# sys-part2.net
KiCad netlist of a schematic drawn in Altium Designer
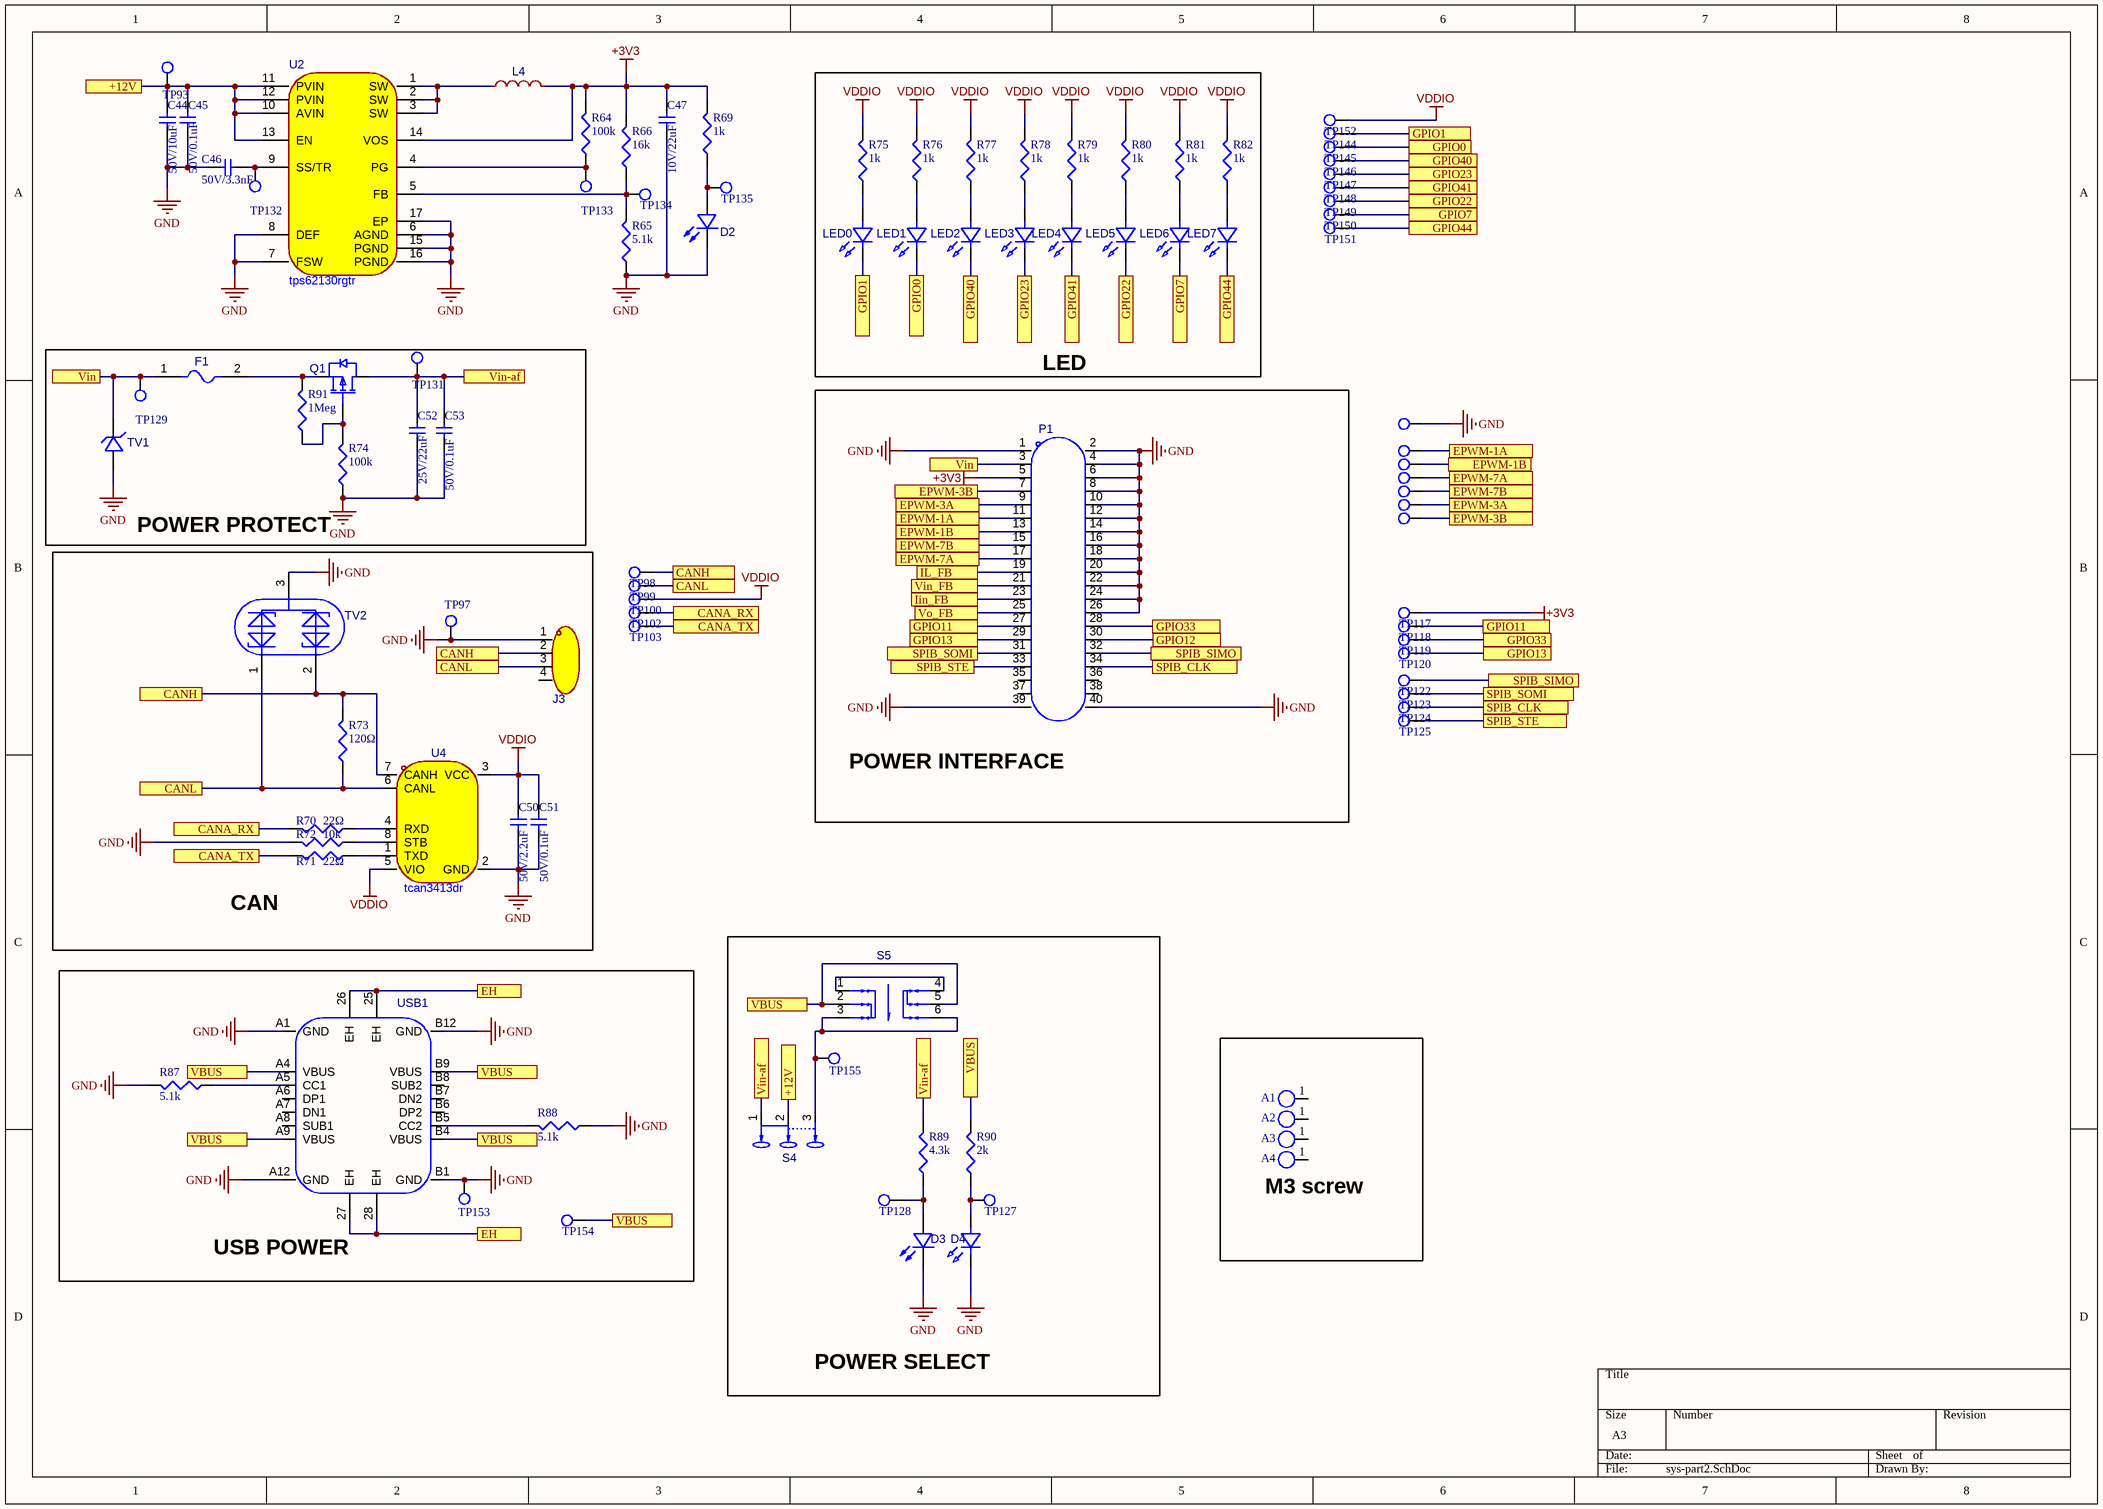
[diagram p0: sys-part2.SchDoc]

(export (version "E")
  (design (tool "Eeschema 10.0.6"))
  (components
    (comp (ref "A1")
      (value "PAD-3.2/6.0")
      (footprint "PAD-3.2/6.0")
      (libsource (lib "60W-PD-V2") (part "PAD-3.2/6.0"))
    )
    (comp (ref "A2")
      (value "PAD-3.2/6.0")
      (footprint "PAD-3.2/6.0")
      (libsource (lib "60W-PD-V2") (part "PAD-3.2/6.0"))
    )
    (comp (ref "A3")
      (value "PAD-3.2/6.0")
      (footprint "PAD-3.2/6.0")
      (libsource (lib "60W-PD-V2") (part "PAD-3.2/6.0"))
    )
    (comp (ref "A4")
      (value "PAD-3.2/6.0")
      (footprint "PAD-3.2/6.0")
      (libsource (lib "60W-PD-V2") (part "PAD-3.2/6.0"))
    )
    (comp (ref "C44")
      (value "50V/10uF")
      (footprint "C0805")
      (description "0805,50V/10uF,")
      (libsource (lib "60W-PD-V2") (part "C0805-50V/10uF"))
    )
    (comp (ref "C45")
      (value "50V/0.1uF")
      (footprint "C0603")
      (description "0603,50V/104")
      (libsource (lib "60W-PD-V2") (part "C0603-50V/104"))
    )
    (comp (ref "C46")
      (value "50V/3.3nF")
      (footprint "C0603")
      (description "0603,50V/3.3nF")
      (libsource (lib "60W-PD-V2") (part "C0603-50V/3.3nF"))
    )
    (comp (ref "C47")
      (value "10V/22uF")
      (footprint "C0603")
      (description "0603,10V/22uF")
      (libsource (lib "60W-PD-V2") (part "C0603-10V/22uF"))
    )
    (comp (ref "C50")
      (value "50V/2.2uF")
      (footprint "C0805")
      (description "0805,50V/2.2uF,")
      (libsource (lib "60W-PD-V2") (part "C0805-50V/2.2uF"))
    )
    (comp (ref "C51")
      (value "50V/0.1uF")
      (footprint "C0603")
      (description "0603,50V/104")
      (libsource (lib "60W-PD-V2") (part "C0603-50V/104"))
    )
    (comp (ref "C52")
      (value "25V/22uF")
      (footprint "C0805")
      (description "0805,25V/22uF,")
      (libsource (lib "60W-PD-V2") (part "C0805-25V/22uF"))
    )
    (comp (ref "C53")
      (value "50V/0.1uF")
      (footprint "C0603")
      (description "0603,50V/104")
      (libsource (lib "60W-PD-V2") (part "C0603-50V/104"))
    )
    (comp (ref "D2")
      (value "ncd0805c1")
      (footprint "LED0805-RD")
      (fields (field (name "MANUFACTURER") "国星光电") (field (name "MANUFACTURERPART") "NCD0805C1"))
      (libsource (lib "60W-PD-V2") (part "ncd0805c1"))
    )
    (comp (ref "D3")
      (value "ncd0805c1")
      (footprint "LED0805-RD")
      (fields (field (name "MANUFACTURER") "国星光电") (field (name "MANUFACTURERPART") "NCD0805C1"))
      (libsource (lib "60W-PD-V2") (part "ncd0805c1"))
    )
    (comp (ref "D4")
      (value "xl-2012surc")
      (footprint "LED0805-RD_RED")
      (fields (field (name "MANUFACTURER") "XINGLIGHT(成兴光)") (field (name "MANUFACTURERPART") "XL-2012SURC"))
      (libsource (lib "60W-PD") (part "xl-2012surc"))
    )
    (comp (ref "F1")
      (value "nsmd050-24v")
      (footprint "F1206")
      (description "耐压(Vmax):24V;最大电流(Imax):100A;保持电流(Ihold):500mA;跳闸电流(Itrip):1A;")
      (fields (field (name "MANUFACTURER") "台湾陆海") (field (name "MANUFACTURERPART") "nSMD050-24V"))
      (libsource (lib "60W-PD-V2") (part "nsmd050-24v"))
    )
    (comp (ref "J3")
      (value "db125-3.81-4p-gn-s")
      (footprint "CONN-TH_DB125-3.81-4P")
      (fields
        (field (name "MANUFACTURER") "DORABO(地博电气)")
        (field (name "MANUFACTURERPART") "DB125-3.81-4P-GN-S")
      )
      (libsource (lib "60W-PD-V2") (part "db125-3.81-4p-gn-s"))
    )
    (comp (ref "L4")
      (value "fhd4020s-3r3mt")
      (footprint "IND-SMD_L4.0-W4.0")
      (description "电感值:3.3uH;精度:±20%;额定电流:4A;饱和电流(Isat):5.9A;类型:绕线电感;")
      (fields (field (name "MANUFACTURER") "cjiang(长江微电)") (field (name "MANUFACTURERPART") "FHD4020S-3R3MT"))
      (libsource (lib "60W-PD-V2") (part "fhd4020s-3r3mt"))
    )
    (comp (ref "LED0")
      (value "xl-2012surc")
      (footprint "LED0805-RD_RED")
      (fields (field (name "MANUFACTURER") "XINGLIGHT(成兴光)") (field (name "MANUFACTURERPART") "XL-2012SURC"))
      (libsource (lib "60W-PD") (part "xl-2012surc"))
    )
    (comp (ref "LED1")
      (value "xl-2012surc")
      (footprint "LED0805-RD_RED")
      (fields (field (name "MANUFACTURER") "XINGLIGHT(成兴光)") (field (name "MANUFACTURERPART") "XL-2012SURC"))
      (libsource (lib "60W-PD") (part "xl-2012surc"))
    )
    (comp (ref "LED2")
      (value "xl-2012surc")
      (footprint "LED0805-RD_RED")
      (fields (field (name "MANUFACTURER") "XINGLIGHT(成兴光)") (field (name "MANUFACTURERPART") "XL-2012SURC"))
      (libsource (lib "60W-PD") (part "xl-2012surc"))
    )
    (comp (ref "LED3")
      (value "xl-2012surc")
      (footprint "LED0805-RD_RED")
      (fields (field (name "MANUFACTURER") "XINGLIGHT(成兴光)") (field (name "MANUFACTURERPART") "XL-2012SURC"))
      (libsource (lib "60W-PD") (part "xl-2012surc"))
    )
    (comp (ref "LED4")
      (value "xl-2012surc")
      (footprint "LED0805-RD_RED")
      (fields (field (name "MANUFACTURER") "XINGLIGHT(成兴光)") (field (name "MANUFACTURERPART") "XL-2012SURC"))
      (libsource (lib "60W-PD") (part "xl-2012surc"))
    )
    (comp (ref "LED5")
      (value "xl-2012surc")
      (footprint "LED0805-RD_RED")
      (fields (field (name "MANUFACTURER") "XINGLIGHT(成兴光)") (field (name "MANUFACTURERPART") "XL-2012SURC"))
      (libsource (lib "60W-PD") (part "xl-2012surc"))
    )
    (comp (ref "LED6")
      (value "xl-2012surc")
      (footprint "LED0805-RD_RED")
      (fields (field (name "MANUFACTURER") "XINGLIGHT(成兴光)") (field (name "MANUFACTURERPART") "XL-2012SURC"))
      (libsource (lib "60W-PD") (part "xl-2012surc"))
    )
    (comp (ref "LED7")
      (value "xl-2012surc")
      (footprint "LED0805-RD_RED")
      (fields (field (name "MANUFACTURER") "XINGLIGHT(成兴光)") (field (name "MANUFACTURERPART") "XL-2012SURC"))
      (libsource (lib "60W-PD") (part "xl-2012surc"))
    )
    (comp (ref "P1")
      (value "zx-pm2.54-2-20py")
      (footprint "HDR-TH_40P-P2.54-V-F-R2-C20-S2.54")
      (fields
        (field (name "MANUFACTURER") "Megastar(兆星)")
        (field (name "MANUFACTURERPART") "ZX-PM2.54-2-20PY")
      )
      (libsource (lib "60W-PD-V2") (part "zx-pm2.54-2-20py"))
    )
    (comp (ref "Q1")
      (value "ao3407a_c15155")
      (footprint "SOT-23-3_L2.9-W1.6-P1.90-LS2.8-BR")
      (fields (field (name "MANUFACTURER") "AOS") (field (name "MANUFACTURERPART") "AO3407A"))
      (libsource (lib "60W-PD-V2") (part "ao3407a_c15155"))
    )
    (comp (ref "R64")
      (value "100k")
      (footprint "R0603")
      (description "0603,100k")
      (libsource (lib "60W-PD-V2") (part "R0603-100k"))
    )
    (comp (ref "R65")
      (value "5.1k")
      (footprint "R0603")
      (description "0603,5.1k")
      (libsource (lib "60W-PD-V2") (part "R0603-5.1k"))
    )
    (comp (ref "R66")
      (value "16k")
      (footprint "R0603")
      (description "0603,16k")
      (libsource (lib "60W-PD-V2") (part "R0603-16k"))
    )
    (comp (ref "R69")
      (value "1k")
      (footprint "R0603")
      (description "0603,1k")
      (libsource (lib "60W-PD-V2") (part "R0603-1k"))
    )
    (comp (ref "R70")
      (value "22Ω")
      (footprint "R0603")
      (description "0603,22Ω")
      (libsource (lib "60W-PD-V2") (part "R0603-22Ω"))
    )
    (comp (ref "R71")
      (value "22Ω")
      (footprint "R0603")
      (description "0603,22Ω")
      (libsource (lib "60W-PD-V2") (part "R0603-22Ω"))
    )
    (comp (ref "R72")
      (value "10k")
      (footprint "R0603")
      (description "0603,10k")
      (libsource (lib "60W-PD-V2") (part "R0603-10k"))
    )
    (comp (ref "R73")
      (value "120Ω")
      (footprint "R0603")
      (description "0603,120Ω")
      (libsource (lib "60W-PD-V2") (part "R0603-120Ω"))
    )
    (comp (ref "R74")
      (value "100k")
      (footprint "R0603")
      (description "0603,100k")
      (libsource (lib "60W-PD-V2") (part "R0603-100k"))
    )
    (comp (ref "R75")
      (value "1k")
      (footprint "R0603")
      (description "0603,1k")
      (libsource (lib "60W-PD-V2") (part "R0603-1k"))
    )
    (comp (ref "R76")
      (value "1k")
      (footprint "R0603")
      (description "0603,1k")
      (libsource (lib "60W-PD-V2") (part "R0603-1k"))
    )
    (comp (ref "R77")
      (value "1k")
      (footprint "R0603")
      (description "0603,1k")
      (libsource (lib "60W-PD-V2") (part "R0603-1k"))
    )
    (comp (ref "R78")
      (value "1k")
      (footprint "R0603")
      (description "0603,1k")
      (libsource (lib "60W-PD-V2") (part "R0603-1k"))
    )
    (comp (ref "R79")
      (value "1k")
      (footprint "R0603")
      (description "0603,1k")
      (libsource (lib "60W-PD-V2") (part "R0603-1k"))
    )
    (comp (ref "R80")
      (value "1k")
      (footprint "R0603")
      (description "0603,1k")
      (libsource (lib "60W-PD-V2") (part "R0603-1k"))
    )
    (comp (ref "R81")
      (value "1k")
      (footprint "R0603")
      (description "0603,1k")
      (libsource (lib "60W-PD-V2") (part "R0603-1k"))
    )
    (comp (ref "R82")
      (value "1k")
      (footprint "R0603")
      (description "0603,1k")
      (libsource (lib "60W-PD-V2") (part "R0603-1k"))
    )
    (comp (ref "R87")
      (value "5.1k")
      (footprint "R0603")
      (description "0603,5.1k")
      (libsource (lib "60W-PD-V2") (part "R0603-5.1k"))
    )
    (comp (ref "R88")
      (value "5.1k")
      (footprint "R0603")
      (description "0603,5.1k")
      (libsource (lib "60W-PD-V2") (part "R0603-5.1k"))
    )
    (comp (ref "R89")
      (value "4.3k")
      (footprint "R0603")
      (description "0603,4.3k")
      (libsource (lib "60W-PD-V2") (part "R0603-4.3k"))
    )
    (comp (ref "R90")
      (value "2k")
      (footprint "R0603")
      (description "0603,2k")
      (libsource (lib "60W-PD-V2") (part "R0603-2k"))
    )
    (comp (ref "R91")
      (value "1Meg")
      (footprint "R0603")
      (description "0603,1Meg")
      (libsource (lib "60W-PD-V2") (part "R0603-1Meg"))
    )
    (comp (ref "S4")
      (value "ss-12d10l5")
      (footprint "SW-TH_SS-12D10L5")
      (description "电路结构:单刀双掷;安装方式:直插;开关颜色:黑色;额定电流:3A;额定电压:125V;工作寿命:1万次;")
      (fields
        (field (name "MANUFACTURER") "XKB Connection(中国星坤)")
        (field (name "MANUFACTURERPART") "SS-12D10L5")
      )
      (libsource (lib "60W-PD") (part "ss-12d10l5"))
    )
    (comp (ref "S5")
      (value "xkb8080-z")
      (footprint "SW-TH_6P-L8.0-W8.0-P2.50")
      (description "自锁/无锁:自锁;安装方式:直插;触点电流:100mA;额定电压:30V;带灯:不带;作用力:1.6N;工作寿命:10万次;")
      (fields
        (field (name "MANUFACTURER") "XKB Connection(中国星坤)")
        (field (name "MANUFACTURERPART") "XKB8080-Z")
      )
      (libsource (lib "60W-PD-V2") (part "xkb8080-z"))
    )
    (comp (ref "TP93")
      (value "TEST POINT")
      (footprint "TP-1.5")
      (libsource (lib "60W-PD") (part "TEST POINT"))
    )
    (comp (ref "TP97")
      (value "TP-pad0.8")
      (footprint "PAD0.8/1.6")
      (libsource (lib "60W-PD-V2") (part "TP-pad0.8"))
    )
    (comp (ref "TP98")
      (value "TEST POINT")
      (footprint "TP-1.5")
      (libsource (lib "60W-PD") (part "TEST POINT"))
    )
    (comp (ref "TP99")
      (value "TEST POINT")
      (footprint "TP-1.5")
      (libsource (lib "60W-PD") (part "TEST POINT"))
    )
    (comp (ref "TP100")
      (value "TEST POINT")
      (footprint "TP-1.5")
      (libsource (lib "60W-PD") (part "TEST POINT"))
    )
    (comp (ref "TP102")
      (value "TEST POINT")
      (footprint "TP-1.5")
      (libsource (lib "60W-PD") (part "TEST POINT"))
    )
    (comp (ref "TP103")
      (value "TEST POINT")
      (footprint "TP-1.5")
      (libsource (lib "60W-PD") (part "TEST POINT"))
    )
    (comp (ref "TP104")
      (value "TP-pad0.8")
      (footprint "PAD0.8/1.6")
      (libsource (lib "60W-PD-V2") (part "TP-pad0.8"))
    )
    (comp (ref "TP105")
      (value "TP-pad0.8")
      (footprint "PAD0.8/1.6")
      (libsource (lib "60W-PD-V2") (part "TP-pad0.8"))
    )
    (comp (ref "TP106")
      (value "TP-pad0.8")
      (footprint "PAD0.8/1.6")
      (libsource (lib "60W-PD-V2") (part "TP-pad0.8"))
    )
    (comp (ref "TP107")
      (value "TP-pad0.8")
      (footprint "PAD0.8/1.6")
      (libsource (lib "60W-PD-V2") (part "TP-pad0.8"))
    )
    (comp (ref "TP108")
      (value "TP-pad0.8")
      (footprint "PAD0.8/1.6")
      (libsource (lib "60W-PD-V2") (part "TP-pad0.8"))
    )
    (comp (ref "TP109")
      (value "TP-pad0.8")
      (footprint "PAD0.8/1.6")
      (libsource (lib "60W-PD-V2") (part "TP-pad0.8"))
    )
    (comp (ref "TP110")
      (value "TP-pad0.8")
      (footprint "PAD0.8/1.6")
      (libsource (lib "60W-PD-V2") (part "TP-pad0.8"))
    )
    (comp (ref "TP117")
      (value "TEST POINT")
      (footprint "TP-1.5")
      (libsource (lib "60W-PD") (part "TEST POINT"))
    )
    (comp (ref "TP118")
      (value "TEST POINT")
      (footprint "TP-1.5")
      (libsource (lib "60W-PD") (part "TEST POINT"))
    )
    (comp (ref "TP119")
      (value "TEST POINT")
      (footprint "TP-1.5")
      (libsource (lib "60W-PD") (part "TEST POINT"))
    )
    (comp (ref "TP120")
      (value "TEST POINT")
      (footprint "TP-1.5")
      (libsource (lib "60W-PD") (part "TEST POINT"))
    )
    (comp (ref "TP122")
      (value "TEST POINT")
      (footprint "TP-1.5")
      (libsource (lib "60W-PD") (part "TEST POINT"))
    )
    (comp (ref "TP123")
      (value "TEST POINT")
      (footprint "TP-1.5")
      (libsource (lib "60W-PD") (part "TEST POINT"))
    )
    (comp (ref "TP124")
      (value "TEST POINT")
      (footprint "TP-1.5")
      (libsource (lib "60W-PD") (part "TEST POINT"))
    )
    (comp (ref "TP125")
      (value "TEST POINT")
      (footprint "TP-1.5")
      (libsource (lib "60W-PD") (part "TEST POINT"))
    )
    (comp (ref "TP127")
      (value "TEST POINT")
      (footprint "TP-1.5")
      (libsource (lib "60W-PD") (part "TEST POINT"))
    )
    (comp (ref "TP128")
      (value "TEST POINT")
      (footprint "TP-1.5")
      (libsource (lib "60W-PD") (part "TEST POINT"))
    )
    (comp (ref "TP129")
      (value "TEST POINT")
      (footprint "TP-1.5")
      (libsource (lib "60W-PD") (part "TEST POINT"))
    )
    (comp (ref "TP131")
      (value "TEST POINT")
      (footprint "TP-1.5")
      (libsource (lib "60W-PD") (part "TEST POINT"))
    )
    (comp (ref "TP132")
      (value "TEST POINT")
      (footprint "TP-1.5")
      (libsource (lib "60W-PD") (part "TEST POINT"))
    )
    (comp (ref "TP133")
      (value "TEST POINT")
      (footprint "TP-1.5")
      (libsource (lib "60W-PD") (part "TEST POINT"))
    )
    (comp (ref "TP134")
      (value "TEST POINT")
      (footprint "TP-1.5")
      (libsource (lib "60W-PD") (part "TEST POINT"))
    )
    (comp (ref "TP135")
      (value "TEST POINT")
      (footprint "TP-1.5")
      (libsource (lib "60W-PD") (part "TEST POINT"))
    )
    (comp (ref "TP144")
      (value "TEST POINT")
      (footprint "TP-1.5")
      (libsource (lib "60W-PD") (part "TEST POINT"))
    )
    (comp (ref "TP145")
      (value "TEST POINT")
      (footprint "TP-1.5")
      (libsource (lib "60W-PD") (part "TEST POINT"))
    )
    (comp (ref "TP146")
      (value "TEST POINT")
      (footprint "TP-1.5")
      (libsource (lib "60W-PD") (part "TEST POINT"))
    )
    (comp (ref "TP147")
      (value "TEST POINT")
      (footprint "TP-1.5")
      (libsource (lib "60W-PD") (part "TEST POINT"))
    )
    (comp (ref "TP148")
      (value "TEST POINT")
      (footprint "TP-1.5")
      (libsource (lib "60W-PD") (part "TEST POINT"))
    )
    (comp (ref "TP149")
      (value "TEST POINT")
      (footprint "TP-1.5")
      (libsource (lib "60W-PD") (part "TEST POINT"))
    )
    (comp (ref "TP150")
      (value "TEST POINT")
      (footprint "TP-1.5")
      (libsource (lib "60W-PD") (part "TEST POINT"))
    )
    (comp (ref "TP151")
      (value "TEST POINT")
      (footprint "TP-1.5")
      (libsource (lib "60W-PD") (part "TEST POINT"))
    )
    (comp (ref "TP152")
      (value "TEST POINT")
      (footprint "TP-1.5")
      (libsource (lib "60W-PD") (part "TEST POINT"))
    )
    (comp (ref "TP153")
      (value "TP-pad0.8")
      (footprint "PAD0.8/1.6")
      (libsource (lib "60W-PD-V2") (part "TP-pad0.8"))
    )
    (comp (ref "TP154")
      (value "TEST POINT")
      (footprint "TP-1.5")
      (libsource (lib "60W-PD") (part "TEST POINT"))
    )
    (comp (ref "TP155")
      (value "TP-pad0.8")
      (footprint "PAD0.8/1.6")
      (libsource (lib "60W-PD-V2") (part "TP-pad0.8"))
    )
    (comp (ref "TV1")
      (value "smbj15a_c83846")
      (footprint "SMB_L4.6-W3.6-LS5.3-RD")
      (description "极性:单向;反向截止电压(Vrwm):15V;钳位电压:24.4V;峰值脉冲电流(Ipp):24.6A;峰值脉冲功率(Ppp):600W;击穿电压(VBR):16.7V;")
      (fields (field (name "MANUFACTURER") "Littelfuse(美国力特)") (field (name "MANUFACTURERPART") "SMBJ15A"))
      (libsource (lib "60W-PD-V2") (part "smbj15a_c83846"))
    )
    (comp (ref "TV2")
      (value "pesd1can,215")
      (footprint "SOT-23_L2.9-W1.3-P1.90-LS2.4-BR")
      (description "极性:双向;反向截止电压(Vrwm):24V;钳位电压:70V;峰值脉冲电流(Ipp):3A@8/20us;峰值脉冲功率(Ppp):200W@8/20us;击穿电压(VBR):27.8V;")
      (fields (field (name "MANUFACTURER") "Nexperia(安世)") (field (name "MANUFACTURERPART") "PESD1CAN,215"))
      (libsource (lib "60W-PD-V2") (part "pesd1can,215"))
    )
    (comp (ref "U2")
      (value "tps62130rgtr")
      (footprint "QFN-16_L3.0-W3.0-P0.50-TL-EP1.7")
      (description "功能类型:降压型;工作电压:3V~17V;输出电压:900mV~6V;输出电流:3A;输出类型:可调;")
      (fields (field (name "MANUFACTURER") "TI(德州仪器)") (field (name "MANUFACTURERPART") "TPS62130RGTR"))
      (libsource (lib "60W-PD-V2") (part "tps62130rgtr"))
    )
    (comp (ref "U4")
      (value "tcan3413dr")
      (footprint "SOP-8_L4.9-W3.9-P1.27-LS6.0-BL-1")
      (description "类型:CAN-FD收发器;数据速率:5Mbps;")
      (fields (field (name "MANUFACTURER") "TI(德州仪器)") (field (name "MANUFACTURERPART") "TCAN3413DR"))
      (libsource (lib "60W-PD-V2") (part "tcan3413dr"))
    )
    (comp (ref "USB1")
      (value "type-c 16p cb1.6 073")
      (footprint "USB-C-SMD_SHOU_TYPE-C-16P-CB1.6")
      (description "连接器类型:Type-C;协议标准:USB 3.1;公母:母;安装方式:沉板;触点数量:16P;端口数量:1;额定电流 - 电源:3A;工作温度:-25℃~+85℃;")
      (fields
        (field (name "MANUFACTURER") "SHOU HAN(首韩)")
        (field (name "MANUFACTURERPART") "TYPE-C 16P CB1.6 073")
      )
      (libsource (lib "60W-PD-V2") (part "type-c 16p cb1.6 073"))
    )
  )
  (nets
    (net (code "1") (name "+3V3") (class "Default")
      (node (ref "C47") (pin "1") (pinfunction "1_1") (pintype "passive"))
      (node (ref "L4") (pin "2") (pinfunction "2_2") (pintype "passive"))
      (node (ref "P1") (pin "5") (pinfunction "5_5") (pintype "passive"))
      (node (ref "R64") (pin "2") (pinfunction "2_2") (pintype "passive"))
      (node (ref "R66") (pin "2") (pinfunction "2_2") (pintype "passive"))
      (node (ref "R69") (pin "2") (pinfunction "2_2") (pintype "passive"))
      (node (ref "TP117") (pin "1") (pinfunction "1_1") (pintype "passive"))
      (node (ref "U2") (pin "14") (pinfunction "VOS_14") (pintype "passive"))
    )
    (net (code "2") (name "/+12V") (class "Default")
      (node (ref "C44") (pin "1") (pinfunction "1_1") (pintype "passive"))
      (node (ref "C45") (pin "1") (pinfunction "1_1") (pintype "passive"))
      (node (ref "S4") (pin "2") (pinfunction "2_2") (pintype "passive"))
      (node (ref "TP93") (pin "1") (pinfunction "1_1") (pintype "passive"))
      (node (ref "U2") (pin "10") (pinfunction "AVIN_10") (pintype "passive"))
      (node (ref "U2") (pin "11") (pinfunction "PVIN_11") (pintype "passive"))
      (node (ref "U2") (pin "12") (pinfunction "PVIN_12") (pintype "passive"))
      (node (ref "U2") (pin "13") (pinfunction "EN_13") (pintype "passive"))
    )
    (net (code "3") (name "/CANA_RX") (class "Default")
      (node (ref "R70") (pin "2") (pinfunction "2_2") (pintype "passive"))
      (node (ref "TP102") (pin "1") (pinfunction "1_1") (pintype "passive"))
    )
    (net (code "4") (name "/CANA_TX") (class "Default")
      (node (ref "R71") (pin "2") (pinfunction "2_2") (pintype "passive"))
      (node (ref "TP103") (pin "1") (pinfunction "1_1") (pintype "passive"))
    )
    (net (code "5") (name "/CANH") (class "Default")
      (node (ref "J3") (pin "2") (pinfunction "2_2") (pintype "passive"))
      (node (ref "R73") (pin "2") (pinfunction "2_2") (pintype "passive"))
      (node (ref "TP98") (pin "1") (pinfunction "1_1") (pintype "passive"))
      (node (ref "TV2") (pin "2") (pinfunction "2_2") (pintype "passive"))
      (node (ref "U4") (pin "7") (pinfunction "CANH_7") (pintype "passive"))
    )
    (net (code "6") (name "/CANL") (class "Default")
      (node (ref "J3") (pin "3") (pinfunction "3_3") (pintype "passive"))
      (node (ref "R73") (pin "1") (pinfunction "1_1") (pintype "passive"))
      (node (ref "TP99") (pin "1") (pinfunction "1_1") (pintype "passive"))
      (node (ref "TV2") (pin "1") (pinfunction "1_1") (pintype "passive"))
      (node (ref "U4") (pin "6") (pinfunction "CANL_6") (pintype "passive"))
    )
    (net (code "7") (name "/EH") (class "Default")
      (node (ref "USB1") (pin "25") (pinfunction "EH_25") (pintype "passive"))
      (node (ref "USB1") (pin "26") (pinfunction "EH_26") (pintype "passive"))
      (node (ref "USB1") (pin "27") (pinfunction "EH_27") (pintype "passive"))
      (node (ref "USB1") (pin "28") (pinfunction "EH_28") (pintype "passive"))
    )
    (net (code "8") (name "/EPWM-1A") (class "Default")
      (node (ref "P1") (pin "11") (pinfunction "11_11") (pintype "passive"))
      (node (ref "TP105") (pin "1") (pinfunction "1_1") (pintype "passive"))
    )
    (net (code "9") (name "/EPWM-1B") (class "Default")
      (node (ref "P1") (pin "13") (pinfunction "13_13") (pintype "passive"))
      (node (ref "TP106") (pin "1") (pinfunction "1_1") (pintype "passive"))
    )
    (net (code "10") (name "/EPWM-3A") (class "Default")
      (node (ref "P1") (pin "9") (pinfunction "9_9") (pintype "passive"))
      (node (ref "TP109") (pin "1") (pinfunction "1_1") (pintype "passive"))
    )
    (net (code "11") (name "/EPWM-3B") (class "Default")
      (node (ref "P1") (pin "7") (pinfunction "7_7") (pintype "passive"))
      (node (ref "TP110") (pin "1") (pinfunction "1_1") (pintype "passive"))
    )
    (net (code "12") (name "/EPWM-7A") (class "Default")
      (node (ref "P1") (pin "17") (pinfunction "17_17") (pintype "passive"))
      (node (ref "TP107") (pin "1") (pinfunction "1_1") (pintype "passive"))
    )
    (net (code "13") (name "/EPWM-7B") (class "Default")
      (node (ref "P1") (pin "15") (pinfunction "15_15") (pintype "passive"))
      (node (ref "TP108") (pin "1") (pinfunction "1_1") (pintype "passive"))
    )
    (net (code "14") (name "/GPIO0") (class "Default")
      (node (ref "LED1") (pin "1") (pinfunction "K_1") (pintype "passive"))
      (node (ref "TP145") (pin "1") (pinfunction "1_1") (pintype "passive"))
    )
    (net (code "15") (name "/GPIO1") (class "Default")
      (node (ref "LED0") (pin "1") (pinfunction "K_1") (pintype "passive"))
      (node (ref "TP144") (pin "1") (pinfunction "1_1") (pintype "passive"))
    )
    (net (code "16") (name "/GPIO7") (class "Default")
      (node (ref "LED6") (pin "1") (pinfunction "K_1") (pintype "passive"))
      (node (ref "TP150") (pin "1") (pinfunction "1_1") (pintype "passive"))
    )
    (net (code "17") (name "/GPIO11") (class "Default")
      (node (ref "P1") (pin "27") (pinfunction "27_27") (pintype "passive"))
      (node (ref "TP118") (pin "1") (pinfunction "1_1") (pintype "passive"))
    )
    (net (code "18") (name "/GPIO12") (class "Default")
      (node (ref "P1") (pin "30") (pinfunction "30_30") (pintype "passive"))
    )
    (net (code "19") (name "/GPIO13") (class "Default")
      (node (ref "P1") (pin "29") (pinfunction "29_29") (pintype "passive"))
      (node (ref "TP120") (pin "1") (pinfunction "1_1") (pintype "passive"))
    )
    (net (code "20") (name "/GPIO22") (class "Default")
      (node (ref "LED5") (pin "1") (pinfunction "K_1") (pintype "passive"))
      (node (ref "TP149") (pin "1") (pinfunction "1_1") (pintype "passive"))
    )
    (net (code "21") (name "/GPIO23") (class "Default")
      (node (ref "LED3") (pin "1") (pinfunction "K_1") (pintype "passive"))
      (node (ref "TP147") (pin "1") (pinfunction "1_1") (pintype "passive"))
    )
    (net (code "22") (name "/GPIO33") (class "Default")
      (node (ref "P1") (pin "28") (pinfunction "28_28") (pintype "passive"))
      (node (ref "TP119") (pin "1") (pinfunction "1_1") (pintype "passive"))
    )
    (net (code "23") (name "/GPIO40") (class "Default")
      (node (ref "LED2") (pin "1") (pinfunction "K_1") (pintype "passive"))
      (node (ref "TP146") (pin "1") (pinfunction "1_1") (pintype "passive"))
    )
    (net (code "24") (name "/GPIO41") (class "Default")
      (node (ref "LED4") (pin "1") (pinfunction "K_1") (pintype "passive"))
      (node (ref "TP148") (pin "1") (pinfunction "1_1") (pintype "passive"))
    )
    (net (code "25") (name "/GPIO44") (class "Default")
      (node (ref "LED7") (pin "1") (pinfunction "K_1") (pintype "passive"))
      (node (ref "TP151") (pin "1") (pinfunction "1_1") (pintype "passive"))
    )
    (net (code "26") (name "/IL_FB") (class "Default")
      (node (ref "P1") (pin "19") (pinfunction "19_19") (pintype "passive"))
    )
    (net (code "27") (name "/Iin_FB") (class "Default")
      (node (ref "P1") (pin "23") (pinfunction "23_23") (pintype "passive"))
    )
    (net (code "28") (name "/SPIB_CLK") (class "Default")
      (node (ref "P1") (pin "34") (pinfunction "34_34") (pintype "passive"))
      (node (ref "TP124") (pin "1") (pinfunction "1_1") (pintype "passive"))
    )
    (net (code "29") (name "/SPIB_SIMO") (class "Default")
      (node (ref "P1") (pin "32") (pinfunction "32_32") (pintype "passive"))
      (node (ref "TP122") (pin "1") (pinfunction "1_1") (pintype "passive"))
    )
    (net (code "30") (name "/SPIB_SOMI") (class "Default")
      (node (ref "P1") (pin "31") (pinfunction "31_31") (pintype "passive"))
      (node (ref "TP123") (pin "1") (pinfunction "1_1") (pintype "passive"))
    )
    (net (code "31") (name "/SPIB_STE") (class "Default")
      (node (ref "P1") (pin "33") (pinfunction "33_33") (pintype "passive"))
      (node (ref "TP125") (pin "1") (pinfunction "1_1") (pintype "passive"))
    )
    (net (code "32") (name "/VBUS") (class "Default")
      (node (ref "R90") (pin "2") (pinfunction "2_2") (pintype "passive"))
      (node (ref "S5") (pin "2") (pinfunction "2_2") (pintype "passive"))
      (node (ref "S5") (pin "5") (pinfunction "5_5") (pintype "passive"))
      (node (ref "TP154") (pin "1") (pinfunction "1_1") (pintype "passive"))
      (node (ref "USB1") (pin "A4") (pinfunction "VBUS_A4") (pintype "passive"))
      (node (ref "USB1") (pin "A9") (pinfunction "VBUS_A9") (pintype "passive"))
      (node (ref "USB1") (pin "B4") (pinfunction "VBUS_B4") (pintype "passive"))
      (node (ref "USB1") (pin "B9") (pinfunction "VBUS_B9") (pintype "passive"))
    )
    (net (code "33") (name "/Vin") (class "Default")
      (node (ref "F1") (pin "1") (pinfunction "1_1") (pintype "passive"))
      (node (ref "P1") (pin "3") (pinfunction "3_3") (pintype "passive"))
      (node (ref "TP129") (pin "1") (pinfunction "1_1") (pintype "passive"))
      (node (ref "TV1") (pin "1") (pinfunction "1_1") (pintype "passive"))
    )
    (net (code "34") (name "/Vin-af") (class "Default")
      (node (ref "C52") (pin "1") (pinfunction "1_1") (pintype "passive"))
      (node (ref "C53") (pin "1") (pinfunction "1_1") (pintype "passive"))
      (node (ref "Q1") (pin "3") (pinfunction "D_3") (pintype "passive"))
      (node (ref "R89") (pin "2") (pinfunction "2_2") (pintype "passive"))
      (node (ref "S4") (pin "1") (pinfunction "1_1") (pintype "passive"))
      (node (ref "TP131") (pin "1") (pinfunction "1_1") (pintype "passive"))
    )
    (net (code "35") (name "/Vin_FB") (class "Default")
      (node (ref "P1") (pin "21") (pinfunction "21_21") (pintype "passive"))
    )
    (net (code "36") (name "/Vo_FB") (class "Default")
      (node (ref "P1") (pin "25") (pinfunction "25_25") (pintype "passive"))
    )
    (net (code "37") (name "GND") (class "Default")
      (node (ref "C44") (pin "2") (pinfunction "2_2") (pintype "passive"))
      (node (ref "C45") (pin "2") (pinfunction "2_2") (pintype "passive"))
      (node (ref "C46") (pin "1") (pinfunction "1_1") (pintype "passive"))
      (node (ref "C47") (pin "2") (pinfunction "2_2") (pintype "passive"))
      (node (ref "C50") (pin "2") (pinfunction "2_2") (pintype "passive"))
      (node (ref "C51") (pin "2") (pinfunction "2_2") (pintype "passive"))
      (node (ref "C52") (pin "2") (pinfunction "2_2") (pintype "passive"))
      (node (ref "C53") (pin "2") (pinfunction "2_2") (pintype "passive"))
      (node (ref "D2") (pin "1") (pinfunction "K_1") (pintype "passive"))
      (node (ref "D3") (pin "1") (pinfunction "K_1") (pintype "passive"))
      (node (ref "D4") (pin "1") (pinfunction "K_1") (pintype "passive"))
      (node (ref "J3") (pin "1") (pinfunction "1_1") (pintype "passive"))
      (node (ref "P1") (pin "1") (pinfunction "1_1") (pintype "passive"))
      (node (ref "P1") (pin "10") (pinfunction "10_10") (pintype "passive"))
      (node (ref "P1") (pin "12") (pinfunction "12_12") (pintype "passive"))
      (node (ref "P1") (pin "14") (pinfunction "14_14") (pintype "passive"))
      (node (ref "P1") (pin "16") (pinfunction "16_16") (pintype "passive"))
      (node (ref "P1") (pin "18") (pinfunction "18_18") (pintype "passive"))
      (node (ref "P1") (pin "2") (pinfunction "2_2") (pintype "passive"))
      (node (ref "P1") (pin "20") (pinfunction "20_20") (pintype "passive"))
      (node (ref "P1") (pin "22") (pinfunction "22_22") (pintype "passive"))
      (node (ref "P1") (pin "24") (pinfunction "24_24") (pintype "passive"))
      (node (ref "P1") (pin "26") (pinfunction "26_26") (pintype "passive"))
      (node (ref "P1") (pin "39") (pinfunction "39_39") (pintype "passive"))
      (node (ref "P1") (pin "4") (pinfunction "4_4") (pintype "passive"))
      (node (ref "P1") (pin "40") (pinfunction "40_40") (pintype "passive"))
      (node (ref "P1") (pin "6") (pinfunction "6_6") (pintype "passive"))
      (node (ref "P1") (pin "8") (pinfunction "8_8") (pintype "passive"))
      (node (ref "R65") (pin "1") (pinfunction "1_1") (pintype "passive"))
      (node (ref "R72") (pin "2") (pinfunction "2_2") (pintype "passive"))
      (node (ref "R74") (pin "1") (pinfunction "1_1") (pintype "passive"))
      (node (ref "R87") (pin "2") (pinfunction "2_2") (pintype "passive"))
      (node (ref "R88") (pin "1") (pinfunction "1_1") (pintype "passive"))
      (node (ref "TP104") (pin "1") (pinfunction "1_1") (pintype "passive"))
      (node (ref "TP153") (pin "1") (pinfunction "1_1") (pintype "passive"))
      (node (ref "TP97") (pin "1") (pinfunction "1_1") (pintype "passive"))
      (node (ref "TV1") (pin "2") (pinfunction "2_2") (pintype "passive"))
      (node (ref "TV2") (pin "3") (pinfunction "3_3") (pintype "passive"))
      (node (ref "U2") (pin "15") (pinfunction "PGND_15") (pintype "passive"))
      (node (ref "U2") (pin "16") (pinfunction "PGND_16") (pintype "passive"))
      (node (ref "U2") (pin "17") (pinfunction "EP_17") (pintype "passive"))
      (node (ref "U2") (pin "6") (pinfunction "AGND_6") (pintype "passive"))
      (node (ref "U2") (pin "7") (pinfunction "FSW_7") (pintype "passive"))
      (node (ref "U2") (pin "8") (pinfunction "DEF_8") (pintype "passive"))
      (node (ref "U4") (pin "2") (pinfunction "GND_2") (pintype "passive"))
      (node (ref "USB1") (pin "A1") (pinfunction "GND_A1") (pintype "passive"))
      (node (ref "USB1") (pin "A12") (pinfunction "GND_A12") (pintype "passive"))
      (node (ref "USB1") (pin "B1") (pinfunction "GND_B1") (pintype "passive"))
      (node (ref "USB1") (pin "B12") (pinfunction "GND_B12") (pintype "passive"))
    )
    (net (code "38") (name "Net-(D2-A)") (class "Default")
      (node (ref "D2") (pin "2") (pinfunction "A_2") (pintype "passive"))
      (node (ref "R69") (pin "1") (pinfunction "1_1") (pintype "passive"))
      (node (ref "TP135") (pin "1") (pinfunction "1_1") (pintype "passive"))
    )
    (net (code "39") (name "Net-(D3-A)") (class "Default")
      (node (ref "D3") (pin "2") (pinfunction "A_2") (pintype "passive"))
      (node (ref "R89") (pin "1") (pinfunction "1_1") (pintype "passive"))
      (node (ref "TP128") (pin "1") (pinfunction "1_1") (pintype "passive"))
    )
    (net (code "40") (name "Net-(D4-A)") (class "Default")
      (node (ref "D4") (pin "2") (pinfunction "A_2") (pintype "passive"))
      (node (ref "R90") (pin "1") (pinfunction "1_1") (pintype "passive"))
      (node (ref "TP127") (pin "1") (pinfunction "1_1") (pintype "passive"))
    )
    (net (code "41") (name "Net-(L4-Pad1)") (class "Default")
      (node (ref "L4") (pin "1") (pinfunction "1_1") (pintype "passive"))
      (node (ref "U2") (pin "1") (pinfunction "SW_1") (pintype "passive"))
      (node (ref "U2") (pin "2") (pinfunction "SW_2") (pintype "passive"))
      (node (ref "U2") (pin "3") (pinfunction "SW_3") (pintype "passive"))
    )
    (net (code "42") (name "Net-(LED0-A)") (class "Default")
      (node (ref "LED0") (pin "2") (pinfunction "A_2") (pintype "passive"))
      (node (ref "R75") (pin "1") (pinfunction "1_1") (pintype "passive"))
    )
    (net (code "43") (name "Net-(LED1-A)") (class "Default")
      (node (ref "LED1") (pin "2") (pinfunction "A_2") (pintype "passive"))
      (node (ref "R76") (pin "1") (pinfunction "1_1") (pintype "passive"))
    )
    (net (code "44") (name "Net-(LED2-A)") (class "Default")
      (node (ref "LED2") (pin "2") (pinfunction "A_2") (pintype "passive"))
      (node (ref "R77") (pin "1") (pinfunction "1_1") (pintype "passive"))
    )
    (net (code "45") (name "Net-(LED3-A)") (class "Default")
      (node (ref "LED3") (pin "2") (pinfunction "A_2") (pintype "passive"))
      (node (ref "R78") (pin "1") (pinfunction "1_1") (pintype "passive"))
    )
    (net (code "46") (name "Net-(LED4-A)") (class "Default")
      (node (ref "LED4") (pin "2") (pinfunction "A_2") (pintype "passive"))
      (node (ref "R79") (pin "1") (pinfunction "1_1") (pintype "passive"))
    )
    (net (code "47") (name "Net-(LED5-A)") (class "Default")
      (node (ref "LED5") (pin "2") (pinfunction "A_2") (pintype "passive"))
      (node (ref "R80") (pin "1") (pinfunction "1_1") (pintype "passive"))
    )
    (net (code "48") (name "Net-(LED6-A)") (class "Default")
      (node (ref "LED6") (pin "2") (pinfunction "A_2") (pintype "passive"))
      (node (ref "R81") (pin "1") (pinfunction "1_1") (pintype "passive"))
    )
    (net (code "49") (name "Net-(LED7-A)") (class "Default")
      (node (ref "LED7") (pin "2") (pinfunction "A_2") (pintype "passive"))
      (node (ref "R82") (pin "1") (pinfunction "1_1") (pintype "passive"))
    )
    (net (code "50") (name "Net-(Q1-G)") (class "Default")
      (node (ref "Q1") (pin "1") (pinfunction "G_1") (pintype "passive"))
      (node (ref "R74") (pin "2") (pinfunction "2_2") (pintype "passive"))
      (node (ref "R91") (pin "1") (pinfunction "1_1") (pintype "passive"))
    )
    (net (code "51") (name "Net-(Q1-S)") (class "Default")
      (node (ref "F1") (pin "2") (pinfunction "2_2") (pintype "passive"))
      (node (ref "Q1") (pin "2") (pinfunction "S_2") (pintype "passive"))
      (node (ref "R91") (pin "2") (pinfunction "2_2") (pintype "passive"))
    )
    (net (code "52") (name "Net-(S4-Pad3)") (class "Default")
      (node (ref "S4") (pin "3") (pinfunction "3_3") (pintype "passive"))
      (node (ref "S5") (pin "3") (pinfunction "3_3") (pintype "passive"))
      (node (ref "S5") (pin "6") (pinfunction "6_6") (pintype "passive"))
      (node (ref "TP155") (pin "1") (pinfunction "1_1") (pintype "passive"))
    )
    (net (code "53") (name "Net-(S5-Pad1)") (class "Default")
      (node (ref "S5") (pin "1") (pinfunction "1_1") (pintype "passive"))
      (node (ref "S5") (pin "4") (pinfunction "4_4") (pintype "passive"))
    )
    (net (code "54") (name "Net-(U2-FB)") (class "Default")
      (node (ref "R65") (pin "2") (pinfunction "2_2") (pintype "passive"))
      (node (ref "R66") (pin "1") (pinfunction "1_1") (pintype "passive"))
      (node (ref "TP134") (pin "1") (pinfunction "1_1") (pintype "passive"))
      (node (ref "U2") (pin "5") (pinfunction "FB_5") (pintype "passive"))
    )
    (net (code "55") (name "Net-(U2-PG)") (class "Default")
      (node (ref "R64") (pin "1") (pinfunction "1_1") (pintype "passive"))
      (node (ref "TP133") (pin "1") (pinfunction "1_1") (pintype "passive"))
      (node (ref "U2") (pin "4") (pinfunction "PG_4") (pintype "passive"))
    )
    (net (code "56") (name "Net-(U2-SS{slash}TR)") (class "Default")
      (node (ref "C46") (pin "2") (pinfunction "2_2") (pintype "passive"))
      (node (ref "TP132") (pin "1") (pinfunction "1_1") (pintype "passive"))
      (node (ref "U2") (pin "9") (pinfunction "SS/TR_9") (pintype "passive"))
    )
    (net (code "57") (name "Net-(U4-RXD)") (class "Default")
      (node (ref "R70") (pin "1") (pinfunction "1_1") (pintype "passive"))
      (node (ref "U4") (pin "4") (pinfunction "RXD_4") (pintype "passive"))
    )
    (net (code "58") (name "Net-(U4-STB)") (class "Default")
      (node (ref "R72") (pin "1") (pinfunction "1_1") (pintype "passive"))
      (node (ref "U4") (pin "8") (pinfunction "STB_8") (pintype "passive"))
    )
    (net (code "59") (name "Net-(U4-TXD)") (class "Default")
      (node (ref "R71") (pin "1") (pinfunction "1_1") (pintype "passive"))
      (node (ref "U4") (pin "1") (pinfunction "TXD_1") (pintype "passive"))
    )
    (net (code "60") (name "Net-(USB1-CC1)") (class "Default")
      (node (ref "R87") (pin "1") (pinfunction "1_1") (pintype "passive"))
      (node (ref "USB1") (pin "A5") (pinfunction "CC1_A5") (pintype "passive"))
    )
    (net (code "61") (name "Net-(USB1-CC2)") (class "Default")
      (node (ref "R88") (pin "2") (pinfunction "2_2") (pintype "passive"))
      (node (ref "USB1") (pin "B5") (pinfunction "CC2_B5") (pintype "passive"))
    )
    (net (code "62") (name "VDDIO") (class "Default")
      (node (ref "C50") (pin "1") (pinfunction "1_1") (pintype "passive"))
      (node (ref "C51") (pin "1") (pinfunction "1_1") (pintype "passive"))
      (node (ref "R75") (pin "2") (pinfunction "2_2") (pintype "passive"))
      (node (ref "R76") (pin "2") (pinfunction "2_2") (pintype "passive"))
      (node (ref "R77") (pin "2") (pinfunction "2_2") (pintype "passive"))
      (node (ref "R78") (pin "2") (pinfunction "2_2") (pintype "passive"))
      (node (ref "R79") (pin "2") (pinfunction "2_2") (pintype "passive"))
      (node (ref "R80") (pin "2") (pinfunction "2_2") (pintype "passive"))
      (node (ref "R81") (pin "2") (pinfunction "2_2") (pintype "passive"))
      (node (ref "R82") (pin "2") (pinfunction "2_2") (pintype "passive"))
      (node (ref "TP100") (pin "1") (pinfunction "1_1") (pintype "passive"))
      (node (ref "TP152") (pin "1") (pinfunction "1_1") (pintype "passive"))
      (node (ref "U4") (pin "3") (pinfunction "VCC_3") (pintype "passive"))
      (node (ref "U4") (pin "5") (pinfunction "VIO_5") (pintype "passive"))
    )
    (net (code "63") (name "unconnected-(A1-Pad1)") (class "Default")
      (node (ref "A1") (pin "1") (pinfunction "1_1") (pintype "passive"))
    )
    (net (code "64") (name "unconnected-(A2-Pad1)") (class "Default")
      (node (ref "A2") (pin "1") (pinfunction "1_1") (pintype "passive"))
    )
    (net (code "65") (name "unconnected-(A3-Pad1)") (class "Default")
      (node (ref "A3") (pin "1") (pinfunction "1_1") (pintype "passive"))
    )
    (net (code "66") (name "unconnected-(A4-Pad1)") (class "Default")
      (node (ref "A4") (pin "1") (pinfunction "1_1") (pintype "passive"))
    )
    (net (code "67") (name "unconnected-(J3-Pad4)") (class "Default")
      (node (ref "J3") (pin "4") (pinfunction "4_4") (pintype "passive"))
    )
    (net (code "68") (name "unconnected-(P1-Pad35)") (class "Default")
      (node (ref "P1") (pin "35") (pinfunction "35_35") (pintype "passive"))
    )
    (net (code "69") (name "unconnected-(P1-Pad36)") (class "Default")
      (node (ref "P1") (pin "36") (pinfunction "36_36") (pintype "passive"))
    )
    (net (code "70") (name "unconnected-(P1-Pad37)") (class "Default")
      (node (ref "P1") (pin "37") (pinfunction "37_37") (pintype "passive"))
    )
    (net (code "71") (name "unconnected-(P1-Pad38)") (class "Default")
      (node (ref "P1") (pin "38") (pinfunction "38_38") (pintype "passive"))
    )
    (net (code "72") (name "unconnected-(USB1-DN1-PadA7)") (class "Default")
      (node (ref "USB1") (pin "A7") (pinfunction "DN1_A7") (pintype "passive"))
    )
    (net (code "73") (name "unconnected-(USB1-DN2-PadB7)") (class "Default")
      (node (ref "USB1") (pin "B7") (pinfunction "DN2_B7") (pintype "passive"))
    )
    (net (code "74") (name "unconnected-(USB1-DP1-PadA6)") (class "Default")
      (node (ref "USB1") (pin "A6") (pinfunction "DP1_A6") (pintype "passive"))
    )
    (net (code "75") (name "unconnected-(USB1-DP2-PadB6)") (class "Default")
      (node (ref "USB1") (pin "B6") (pinfunction "DP2_B6") (pintype "passive"))
    )
    (net (code "76") (name "unconnected-(USB1-SUB1-PadA8)") (class "Default")
      (node (ref "USB1") (pin "A8") (pinfunction "SUB1_A8") (pintype "passive"))
    )
    (net (code "77") (name "unconnected-(USB1-SUB2-PadB8)") (class "Default")
      (node (ref "USB1") (pin "B8") (pinfunction "SUB2_B8") (pintype "passive"))
    )
  )
)
